# CNC_Remote.net
KiCad netlist of a schematic drawn in EAGLE
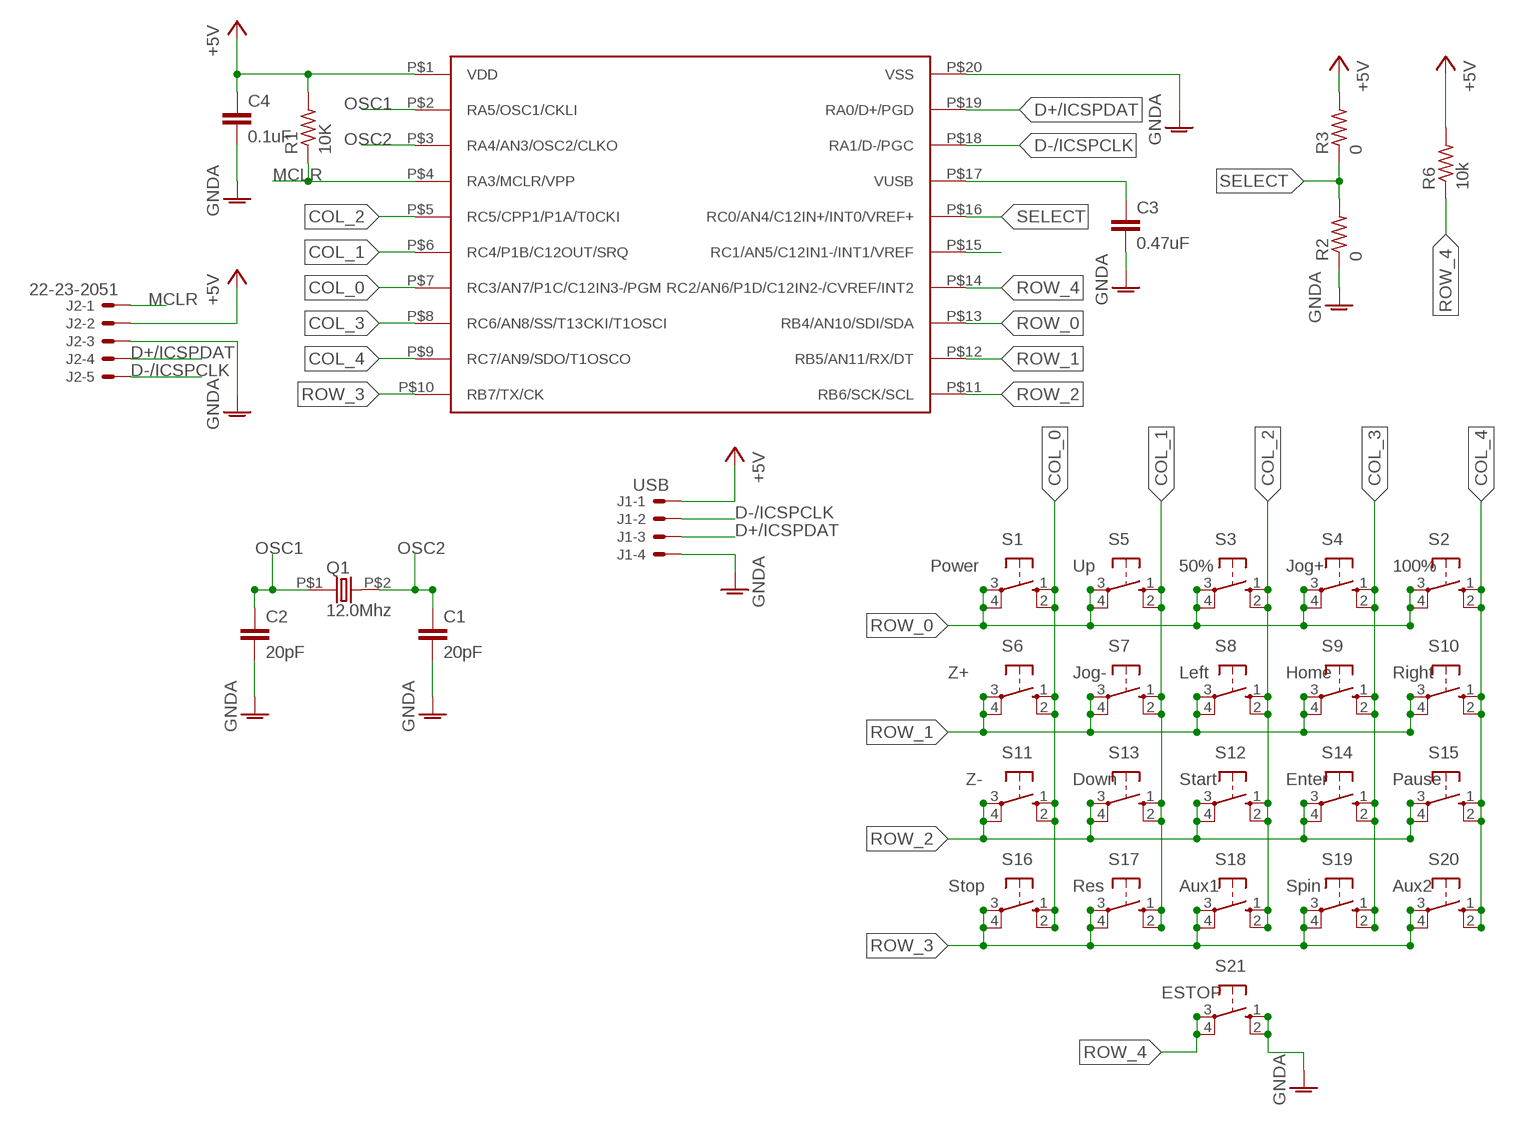
[diagram p0: schematic, sheet 1]

(export (version "E")
  (design (tool "Eeschema 10.0.6"))
  (components
    (comp (ref "C1")
      (value "20pF")
      (footprint "eagle-import:C0603")
      (libsource (lib "eagle-import") (part "C-EUC0603"))
    )
    (comp (ref "C2")
      (value "20pF")
      (footprint "eagle-import:C0603")
      (libsource (lib "eagle-import") (part "C-EUC0603"))
    )
    (comp (ref "C3")
      (value "0.47uF")
      (footprint "eagle-import:C0603")
      (libsource (lib "eagle-import") (part "C-EUC0603"))
    )
    (comp (ref "C4")
      (value "0.1uF")
      (footprint "eagle-import:C0603")
      (libsource (lib "eagle-import") (part "C-EUC0603"))
    )
    (comp (ref "J1")
      (value "USB")
      (footprint "eagle-import:22-23-2041")
      (fields (field (name "MF") "MOLEX") (field (name "MPN") "22-23-2041"))
      (libsource (lib "eagle-import") (part "22-23-2041"))
    )
    (comp (ref "J2")
      (value "22-23-2051")
      (footprint "eagle-import:22-23-2051")
      (fields (field (name "MF") "MOLEX"))
      (libsource (lib "eagle-import") (part "22-23-2051"))
    )
    (comp (ref "Q1")
      (value "12.0Mhz")
      (footprint "eagle-import:HC49_US")
      (libsource (lib "eagle-import") (part "CSM-3X"))
    )
    (comp (ref "R1")
      (value "10K")
      (footprint "eagle-import:R0603")
      (libsource (lib "eagle-import") (part "R-US_R0603"))
    )
    (comp (ref "R2")
      (value "0")
      (footprint "eagle-import:R0603")
      (libsource (lib "eagle-import") (part "R-US_R0603"))
    )
    (comp (ref "R3")
      (value "0")
      (footprint "eagle-import:R0603")
      (libsource (lib "eagle-import") (part "R-US_R0603"))
    )
    (comp (ref "R6")
      (value "10k")
      (footprint "eagle-import:R0603")
      (libsource (lib "eagle-import") (part "R-US_R0603"))
    )
    (comp (ref "S1")
      (value "10-XX")
      (footprint "eagle-import:B3F-10XX")
      (fields (field (name "MPN") "B3F-1000"))
      (libsource (lib "eagle-import") (part "10-XX"))
    )
    (comp (ref "S2")
      (value "10-XX")
      (footprint "eagle-import:B3F-10XX")
      (fields (field (name "MPN") "B3F-1000"))
      (libsource (lib "eagle-import") (part "10-XX"))
    )
    (comp (ref "S3")
      (value "10-XX")
      (footprint "eagle-import:B3F-10XX")
      (fields (field (name "MPN") "B3F-1000"))
      (libsource (lib "eagle-import") (part "10-XX"))
    )
    (comp (ref "S4")
      (value "10-XX")
      (footprint "eagle-import:B3F-10XX")
      (fields (field (name "MPN") "B3F-1000"))
      (libsource (lib "eagle-import") (part "10-XX"))
    )
    (comp (ref "S5")
      (value "10-XX")
      (footprint "eagle-import:B3F-10XX")
      (fields (field (name "MPN") "B3F-1000"))
      (libsource (lib "eagle-import") (part "10-XX"))
    )
    (comp (ref "S6")
      (value "10-XX")
      (footprint "eagle-import:B3F-10XX")
      (fields (field (name "MPN") "B3F-1000"))
      (libsource (lib "eagle-import") (part "10-XX"))
    )
    (comp (ref "S7")
      (value "10-XX")
      (footprint "eagle-import:B3F-10XX")
      (fields (field (name "MPN") "B3F-1000"))
      (libsource (lib "eagle-import") (part "10-XX"))
    )
    (comp (ref "S8")
      (value "10-XX")
      (footprint "eagle-import:B3F-10XX")
      (fields (field (name "MPN") "B3F-1000"))
      (libsource (lib "eagle-import") (part "10-XX"))
    )
    (comp (ref "S9")
      (value "10-XX")
      (footprint "eagle-import:B3F-10XX")
      (fields (field (name "MPN") "B3F-1000"))
      (libsource (lib "eagle-import") (part "10-XX"))
    )
    (comp (ref "S10")
      (value "10-XX")
      (footprint "eagle-import:B3F-10XX")
      (fields (field (name "MPN") "B3F-1000"))
      (libsource (lib "eagle-import") (part "10-XX"))
    )
    (comp (ref "S11")
      (value "10-XX")
      (footprint "eagle-import:B3F-10XX")
      (fields (field (name "MPN") "B3F-1000"))
      (libsource (lib "eagle-import") (part "10-XX"))
    )
    (comp (ref "S12")
      (value "10-XX")
      (footprint "eagle-import:B3F-10XX")
      (fields (field (name "MPN") "B3F-1000"))
      (libsource (lib "eagle-import") (part "10-XX"))
    )
    (comp (ref "S13")
      (value "10-XX")
      (footprint "eagle-import:B3F-10XX")
      (fields (field (name "MPN") "B3F-1000"))
      (libsource (lib "eagle-import") (part "10-XX"))
    )
    (comp (ref "S14")
      (value "10-XX")
      (footprint "eagle-import:B3F-10XX")
      (fields (field (name "MPN") "B3F-1000"))
      (libsource (lib "eagle-import") (part "10-XX"))
    )
    (comp (ref "S15")
      (value "10-XX")
      (footprint "eagle-import:B3F-10XX")
      (fields (field (name "MPN") "B3F-1000"))
      (libsource (lib "eagle-import") (part "10-XX"))
    )
    (comp (ref "S16")
      (value "10-XX")
      (footprint "eagle-import:B3F-10XX")
      (fields (field (name "MPN") "B3F-1000"))
      (libsource (lib "eagle-import") (part "10-XX"))
    )
    (comp (ref "S17")
      (value "10-XX")
      (footprint "eagle-import:B3F-10XX")
      (fields (field (name "MPN") "B3F-1000"))
      (libsource (lib "eagle-import") (part "10-XX"))
    )
    (comp (ref "S18")
      (value "10-XX")
      (footprint "eagle-import:B3F-10XX")
      (fields (field (name "MPN") "B3F-1000"))
      (libsource (lib "eagle-import") (part "10-XX"))
    )
    (comp (ref "S19")
      (value "10-XX")
      (footprint "eagle-import:B3F-10XX")
      (fields (field (name "MPN") "B3F-1000"))
      (libsource (lib "eagle-import") (part "10-XX"))
    )
    (comp (ref "S20")
      (value "10-XX")
      (footprint "eagle-import:B3F-10XX")
      (fields (field (name "MPN") "B3F-1000"))
      (libsource (lib "eagle-import") (part "10-XX"))
    )
    (comp (ref "S21")
      (value "10-XX")
      (footprint "eagle-import:B3F-10XX")
      (fields (field (name "MPN") "B3F-1000"))
      (libsource (lib "eagle-import") (part "10-XX"))
    )
    (comp (ref "U1")
      (value "PIC18F1K50SOIC")
      (footprint "eagle-import:SOIC-20")
      (libsource (lib "eagle-import") (part "PIC18F1K50SOIC"))
    )
  )
  (nets
    (net (code "1") (name "+5V") (class "Default")
      (node (ref "C4") (pin "1") (pinfunction "1_1") (pintype "passive"))
      (node (ref "J1") (pin "1") (pinfunction "S_1") (pintype "passive"))
      (node (ref "J2") (pin "2") (pinfunction "S_2") (pintype "passive"))
      (node (ref "R1") (pin "2") (pinfunction "2_2") (pintype "passive"))
      (node (ref "R3") (pin "2") (pinfunction "2_2") (pintype "passive"))
      (node (ref "R6") (pin "2") (pinfunction "2_2") (pintype "passive"))
      (node (ref "U1") (pin "P$1") (pinfunction "VDD_P$1") (pintype "bidirectional"))
    )
    (net (code "2") (name "/MCLR") (class "Default")
      (node (ref "J2") (pin "1") (pinfunction "S_1") (pintype "passive"))
      (node (ref "R1") (pin "1") (pinfunction "1_1") (pintype "passive"))
      (node (ref "U1") (pin "P$4") (pinfunction "RA3/MCLR/VPP_P$4") (pintype "bidirectional"))
    )
    (net (code "3") (name "/OSC1") (class "Default")
      (node (ref "C2") (pin "1") (pinfunction "1_1") (pintype "passive"))
      (node (ref "Q1") (pin "P$1") (pinfunction "1_P$1") (pintype "passive"))
      (node (ref "U1") (pin "P$2") (pinfunction "RA5/OSC1/CKLI_P$2") (pintype "bidirectional"))
    )
    (net (code "4") (name "/OSC2") (class "Default")
      (node (ref "C1") (pin "1") (pinfunction "1_1") (pintype "passive"))
      (node (ref "Q1") (pin "P$2") (pinfunction "2_P$2") (pintype "passive"))
      (node (ref "U1") (pin "P$3") (pinfunction "RA4/AN3/OSC2/CLKO_P$3") (pintype "bidirectional"))
    )
    (net (code "5") (name "COL_0") (class "Default")
      (node (ref "S1") (pin "1") (pinfunction "S_1") (pintype "passive"))
      (node (ref "S1") (pin "2") (pinfunction "S1_2") (pintype "passive"))
      (node (ref "S11") (pin "1") (pinfunction "S_1") (pintype "passive"))
      (node (ref "S11") (pin "2") (pinfunction "S1_2") (pintype "passive"))
      (node (ref "S16") (pin "1") (pinfunction "S_1") (pintype "passive"))
      (node (ref "S16") (pin "2") (pinfunction "S1_2") (pintype "passive"))
      (node (ref "S6") (pin "1") (pinfunction "S_1") (pintype "passive"))
      (node (ref "S6") (pin "2") (pinfunction "S1_2") (pintype "passive"))
      (node (ref "U1") (pin "P$7") (pinfunction "RC3/AN7/P1C/C12IN3-/PGM_P$7") (pintype "bidirectional"))
    )
    (net (code "6") (name "COL_1") (class "Default")
      (node (ref "S13") (pin "1") (pinfunction "S_1") (pintype "passive"))
      (node (ref "S13") (pin "2") (pinfunction "S1_2") (pintype "passive"))
      (node (ref "S17") (pin "1") (pinfunction "S_1") (pintype "passive"))
      (node (ref "S17") (pin "2") (pinfunction "S1_2") (pintype "passive"))
      (node (ref "S5") (pin "1") (pinfunction "S_1") (pintype "passive"))
      (node (ref "S5") (pin "2") (pinfunction "S1_2") (pintype "passive"))
      (node (ref "S7") (pin "1") (pinfunction "S_1") (pintype "passive"))
      (node (ref "S7") (pin "2") (pinfunction "S1_2") (pintype "passive"))
      (node (ref "U1") (pin "P$6") (pinfunction "RC4/P1B/C12OUT/SRQ_P$6") (pintype "bidirectional"))
    )
    (net (code "7") (name "COL_2") (class "Default")
      (node (ref "S12") (pin "1") (pinfunction "S_1") (pintype "passive"))
      (node (ref "S12") (pin "2") (pinfunction "S1_2") (pintype "passive"))
      (node (ref "S18") (pin "1") (pinfunction "S_1") (pintype "passive"))
      (node (ref "S18") (pin "2") (pinfunction "S1_2") (pintype "passive"))
      (node (ref "S3") (pin "1") (pinfunction "S_1") (pintype "passive"))
      (node (ref "S3") (pin "2") (pinfunction "S1_2") (pintype "passive"))
      (node (ref "S8") (pin "1") (pinfunction "S_1") (pintype "passive"))
      (node (ref "S8") (pin "2") (pinfunction "S1_2") (pintype "passive"))
      (node (ref "U1") (pin "P$5") (pinfunction "RC5/CPP1/P1A/T0CKI_P$5") (pintype "bidirectional"))
    )
    (net (code "8") (name "COL_3") (class "Default")
      (node (ref "S14") (pin "1") (pinfunction "S_1") (pintype "passive"))
      (node (ref "S14") (pin "2") (pinfunction "S1_2") (pintype "passive"))
      (node (ref "S19") (pin "1") (pinfunction "S_1") (pintype "passive"))
      (node (ref "S19") (pin "2") (pinfunction "S1_2") (pintype "passive"))
      (node (ref "S4") (pin "1") (pinfunction "S_1") (pintype "passive"))
      (node (ref "S4") (pin "2") (pinfunction "S1_2") (pintype "passive"))
      (node (ref "S9") (pin "1") (pinfunction "S_1") (pintype "passive"))
      (node (ref "S9") (pin "2") (pinfunction "S1_2") (pintype "passive"))
      (node (ref "U1") (pin "P$8") (pinfunction "RC6/AN8/SS/T13CKI/T1OSCI_P$8") (pintype "bidirectional"))
    )
    (net (code "9") (name "COL_4") (class "Default")
      (node (ref "S10") (pin "1") (pinfunction "S_1") (pintype "passive"))
      (node (ref "S10") (pin "2") (pinfunction "S1_2") (pintype "passive"))
      (node (ref "S15") (pin "1") (pinfunction "S_1") (pintype "passive"))
      (node (ref "S15") (pin "2") (pinfunction "S1_2") (pintype "passive"))
      (node (ref "S2") (pin "1") (pinfunction "S_1") (pintype "passive"))
      (node (ref "S2") (pin "2") (pinfunction "S1_2") (pintype "passive"))
      (node (ref "S20") (pin "1") (pinfunction "S_1") (pintype "passive"))
      (node (ref "S20") (pin "2") (pinfunction "S1_2") (pintype "passive"))
      (node (ref "U1") (pin "P$9") (pinfunction "RC7/AN9/SDO/T1OSCO_P$9") (pintype "bidirectional"))
    )
    (net (code "10") (name "D+{slash}ICSPDAT") (class "Default")
      (node (ref "J1") (pin "3") (pinfunction "S_3") (pintype "passive"))
      (node (ref "J2") (pin "4") (pinfunction "S_4") (pintype "passive"))
      (node (ref "U1") (pin "P$19") (pinfunction "RA0/D+/PGD_P$19") (pintype "bidirectional"))
    )
    (net (code "11") (name "D-{slash}ICSPCLK") (class "Default")
      (node (ref "J1") (pin "2") (pinfunction "S_2") (pintype "passive"))
      (node (ref "J2") (pin "5") (pinfunction "S_5") (pintype "passive"))
      (node (ref "U1") (pin "P$18") (pinfunction "RA1/D-/PGC_P$18") (pintype "bidirectional"))
    )
    (net (code "12") (name "GNDA") (class "Default")
      (node (ref "C1") (pin "2") (pinfunction "2_2") (pintype "passive"))
      (node (ref "C2") (pin "2") (pinfunction "2_2") (pintype "passive"))
      (node (ref "C3") (pin "2") (pinfunction "2_2") (pintype "passive"))
      (node (ref "C4") (pin "2") (pinfunction "2_2") (pintype "passive"))
      (node (ref "J1") (pin "4") (pinfunction "S_4") (pintype "passive"))
      (node (ref "J2") (pin "3") (pinfunction "S_3") (pintype "passive"))
      (node (ref "R2") (pin "1") (pinfunction "1_1") (pintype "passive"))
      (node (ref "S21") (pin "1") (pinfunction "S_1") (pintype "passive"))
      (node (ref "S21") (pin "2") (pinfunction "S1_2") (pintype "passive"))
      (node (ref "U1") (pin "P$20") (pinfunction "VSS_P$20") (pintype "bidirectional"))
    )
    (net (code "13") (name "Net-(U1-VUSB)") (class "Default")
      (node (ref "C3") (pin "1") (pinfunction "1_1") (pintype "passive"))
      (node (ref "U1") (pin "P$17") (pinfunction "VUSB_P$17") (pintype "bidirectional"))
    )
    (net (code "14") (name "ROW_0") (class "Default")
      (node (ref "S1") (pin "3") (pinfunction "P_3") (pintype "passive"))
      (node (ref "S1") (pin "4") (pinfunction "P1_4") (pintype "passive"))
      (node (ref "S2") (pin "3") (pinfunction "P_3") (pintype "passive"))
      (node (ref "S2") (pin "4") (pinfunction "P1_4") (pintype "passive"))
      (node (ref "S3") (pin "3") (pinfunction "P_3") (pintype "passive"))
      (node (ref "S3") (pin "4") (pinfunction "P1_4") (pintype "passive"))
      (node (ref "S4") (pin "3") (pinfunction "P_3") (pintype "passive"))
      (node (ref "S4") (pin "4") (pinfunction "P1_4") (pintype "passive"))
      (node (ref "S5") (pin "3") (pinfunction "P_3") (pintype "passive"))
      (node (ref "S5") (pin "4") (pinfunction "P1_4") (pintype "passive"))
      (node (ref "U1") (pin "P$13") (pinfunction "RB4/AN10/SDI/SDA_P$13") (pintype "bidirectional"))
    )
    (net (code "15") (name "ROW_1") (class "Default")
      (node (ref "S10") (pin "3") (pinfunction "P_3") (pintype "passive"))
      (node (ref "S10") (pin "4") (pinfunction "P1_4") (pintype "passive"))
      (node (ref "S6") (pin "3") (pinfunction "P_3") (pintype "passive"))
      (node (ref "S6") (pin "4") (pinfunction "P1_4") (pintype "passive"))
      (node (ref "S7") (pin "3") (pinfunction "P_3") (pintype "passive"))
      (node (ref "S7") (pin "4") (pinfunction "P1_4") (pintype "passive"))
      (node (ref "S8") (pin "3") (pinfunction "P_3") (pintype "passive"))
      (node (ref "S8") (pin "4") (pinfunction "P1_4") (pintype "passive"))
      (node (ref "S9") (pin "3") (pinfunction "P_3") (pintype "passive"))
      (node (ref "S9") (pin "4") (pinfunction "P1_4") (pintype "passive"))
      (node (ref "U1") (pin "P$12") (pinfunction "RB5/AN11/RX/DT_P$12") (pintype "bidirectional"))
    )
    (net (code "16") (name "ROW_2") (class "Default")
      (node (ref "S11") (pin "3") (pinfunction "P_3") (pintype "passive"))
      (node (ref "S11") (pin "4") (pinfunction "P1_4") (pintype "passive"))
      (node (ref "S12") (pin "3") (pinfunction "P_3") (pintype "passive"))
      (node (ref "S12") (pin "4") (pinfunction "P1_4") (pintype "passive"))
      (node (ref "S13") (pin "3") (pinfunction "P_3") (pintype "passive"))
      (node (ref "S13") (pin "4") (pinfunction "P1_4") (pintype "passive"))
      (node (ref "S14") (pin "3") (pinfunction "P_3") (pintype "passive"))
      (node (ref "S14") (pin "4") (pinfunction "P1_4") (pintype "passive"))
      (node (ref "S15") (pin "3") (pinfunction "P_3") (pintype "passive"))
      (node (ref "S15") (pin "4") (pinfunction "P1_4") (pintype "passive"))
      (node (ref "U1") (pin "P$11") (pinfunction "RB6/SCK/SCL_P$11") (pintype "bidirectional"))
    )
    (net (code "17") (name "ROW_3") (class "Default")
      (node (ref "S16") (pin "3") (pinfunction "P_3") (pintype "passive"))
      (node (ref "S16") (pin "4") (pinfunction "P1_4") (pintype "passive"))
      (node (ref "S17") (pin "3") (pinfunction "P_3") (pintype "passive"))
      (node (ref "S17") (pin "4") (pinfunction "P1_4") (pintype "passive"))
      (node (ref "S18") (pin "3") (pinfunction "P_3") (pintype "passive"))
      (node (ref "S18") (pin "4") (pinfunction "P1_4") (pintype "passive"))
      (node (ref "S19") (pin "3") (pinfunction "P_3") (pintype "passive"))
      (node (ref "S19") (pin "4") (pinfunction "P1_4") (pintype "passive"))
      (node (ref "S20") (pin "3") (pinfunction "P_3") (pintype "passive"))
      (node (ref "S20") (pin "4") (pinfunction "P1_4") (pintype "passive"))
      (node (ref "U1") (pin "P$10") (pinfunction "RB7/TX/CK_P$10") (pintype "bidirectional"))
    )
    (net (code "18") (name "ROW_4") (class "Default")
      (node (ref "R6") (pin "1") (pinfunction "1_1") (pintype "passive"))
      (node (ref "S21") (pin "3") (pinfunction "P_3") (pintype "passive"))
      (node (ref "S21") (pin "4") (pinfunction "P1_4") (pintype "passive"))
      (node (ref "U1") (pin "P$14") (pinfunction "RC2/AN6/P1D/C12IN2-/CVREF/INT2_P$14") (pintype "bidirectional"))
    )
    (net (code "19") (name "SELECT") (class "Default")
      (node (ref "R2") (pin "2") (pinfunction "2_2") (pintype "passive"))
      (node (ref "R3") (pin "1") (pinfunction "1_1") (pintype "passive"))
      (node (ref "U1") (pin "P$16") (pinfunction "RC0/AN4/C12IN+/INT0/VREF+_P$16") (pintype "bidirectional"))
    )
    (net (code "20") (name "unconnected-(U1-RC1{slash}AN5{slash}C12IN1-{slash}INT1{slash}VREF-PadP$15)") (class "Default")
      (node (ref "U1") (pin "P$15") (pinfunction "RC1/AN5/C12IN1-/INT1/VREF_P$15") (pintype "bidirectional"))
    )
  )
)
